# main.net
KiCad netlist of a schematic drawn in Altium Designer
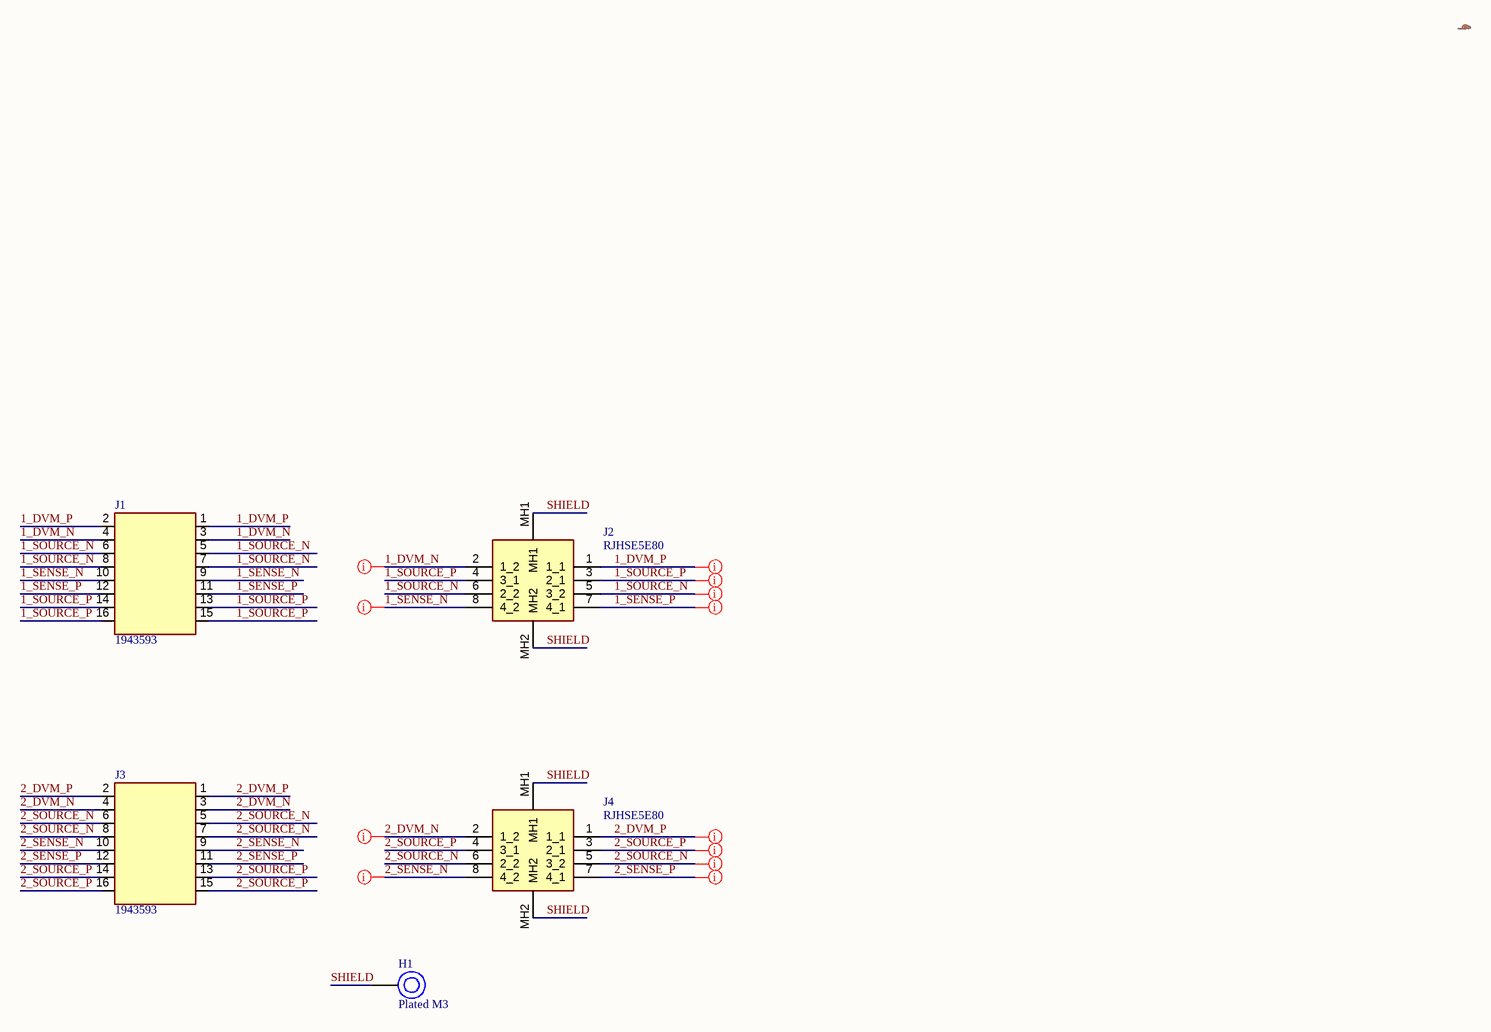
[diagram p0: main.SchDoc]

(export (version "E")
  (design (tool "Eeschema 10.0.6"))
  (components
    (comp (ref "H1")
      (value "Plated M3")
      (footprint "MountingHole_3.2mm_M3_Pad_Via_Unplated")
      (libsource (lib "jlofw") (part "mounting_hole_pad"))
    )
    (comp (ref "J1")
      (value "phoenix_1943593")
      (footprint "phoenix_1943593")
      (description "Block Header Female  5.08mm Vertical TH")
      (fields (field (name "MANUFACTURER P/N") "1943593") (field (name "MANUFACTURER") "Phoenix Contact"))
      (libsource (lib "jlofw") (part "phoenix_1943593"))
    )
    (comp (ref "J2")
      (value "amphenol_RJHSE5E80")
      (footprint "amphenol_RJHSE5E80")
      (description "RJ45 90° Angle Right Shielded")
      (fields (field (name "MANUFACTURER P/N") "RJHSE5E80") (field (name "MANUFACTURER") "Amphenol ICC"))
      (libsource (lib "jlofw") (part "amphenol_RJHSE5E80"))
    )
    (comp (ref "J3")
      (value "phoenix_1943593")
      (footprint "phoenix_1943593")
      (description "Block Header Female  5.08mm Vertical TH")
      (fields (field (name "MANUFACTURER P/N") "1943593") (field (name "MANUFACTURER") "Phoenix Contact"))
      (libsource (lib "jlofw") (part "phoenix_1943593"))
    )
    (comp (ref "J4")
      (value "amphenol_RJHSE5E80")
      (footprint "amphenol_RJHSE5E80")
      (description "RJ45 90° Angle Right Shielded")
      (fields (field (name "MANUFACTURER P/N") "RJHSE5E80") (field (name "MANUFACTURER") "Amphenol ICC"))
      (libsource (lib "jlofw") (part "amphenol_RJHSE5E80"))
    )
    (comp (ref "logo1") (value "beaver") (footprint "beaver") (libsource (lib "jlofw") (part "beaver")))
  )
  (nets
    (net (code "1") (name "/1_DVM_N") (class "Default")
      (node (ref "J1") (pin "3") (pinfunction "2.1_3") (pintype "passive"))
      (node (ref "J1") (pin "4") (pinfunction "2.2_4") (pintype "passive"))
      (node (ref "J2") (pin "2") (pinfunction "1_2_2") (pintype "passive"))
    )
    (net (code "2") (name "/1_DVM_P") (class "Default")
      (node (ref "J1") (pin "1") (pinfunction "1.1_1") (pintype "passive"))
      (node (ref "J1") (pin "2") (pinfunction "1.2_2") (pintype "passive"))
      (node (ref "J2") (pin "1") (pinfunction "1_1_1") (pintype "passive"))
    )
    (net (code "3") (name "/1_SENSE_N") (class "Default")
      (node (ref "J1") (pin "10") (pinfunction "5.2_10") (pintype "passive"))
      (node (ref "J1") (pin "9") (pinfunction "5.1_9") (pintype "passive"))
      (node (ref "J2") (pin "8") (pinfunction "4_2_8") (pintype "passive"))
    )
    (net (code "4") (name "/1_SENSE_P") (class "Default")
      (node (ref "J1") (pin "11") (pinfunction "6.1_11") (pintype "passive"))
      (node (ref "J1") (pin "12") (pinfunction "6.2_12") (pintype "passive"))
      (node (ref "J2") (pin "7") (pinfunction "4_1_7") (pintype "passive"))
    )
    (net (code "5") (name "/1_SOURCE_N") (class "Default")
      (node (ref "J1") (pin "5") (pinfunction "3.1_5") (pintype "passive"))
      (node (ref "J1") (pin "6") (pinfunction "3.2_6") (pintype "passive"))
      (node (ref "J1") (pin "7") (pinfunction "4.1_7") (pintype "passive"))
      (node (ref "J1") (pin "8") (pinfunction "4.2_8") (pintype "passive"))
      (node (ref "J2") (pin "5") (pinfunction "3_2_5") (pintype "passive"))
      (node (ref "J2") (pin "6") (pinfunction "2_2_6") (pintype "passive"))
    )
    (net (code "6") (name "/1_SOURCE_P") (class "Default")
      (node (ref "J1") (pin "13") (pinfunction "7.1_13") (pintype "passive"))
      (node (ref "J1") (pin "14") (pinfunction "7.2_14") (pintype "passive"))
      (node (ref "J1") (pin "15") (pinfunction "8.1_15") (pintype "passive"))
      (node (ref "J1") (pin "16") (pinfunction "8.2_16") (pintype "passive"))
      (node (ref "J2") (pin "3") (pinfunction "2_1_3") (pintype "passive"))
      (node (ref "J2") (pin "4") (pinfunction "3_1_4") (pintype "passive"))
    )
    (net (code "7") (name "/2_DVM_N") (class "Default")
      (node (ref "J3") (pin "3") (pinfunction "2.1_3") (pintype "passive"))
      (node (ref "J3") (pin "4") (pinfunction "2.2_4") (pintype "passive"))
      (node (ref "J4") (pin "2") (pinfunction "1_2_2") (pintype "passive"))
    )
    (net (code "8") (name "/2_DVM_P") (class "Default")
      (node (ref "J3") (pin "1") (pinfunction "1.1_1") (pintype "passive"))
      (node (ref "J3") (pin "2") (pinfunction "1.2_2") (pintype "passive"))
      (node (ref "J4") (pin "1") (pinfunction "1_1_1") (pintype "passive"))
    )
    (net (code "9") (name "/2_SENSE_N") (class "Default")
      (node (ref "J3") (pin "10") (pinfunction "5.2_10") (pintype "passive"))
      (node (ref "J3") (pin "9") (pinfunction "5.1_9") (pintype "passive"))
      (node (ref "J4") (pin "8") (pinfunction "4_2_8") (pintype "passive"))
    )
    (net (code "10") (name "/2_SENSE_P") (class "Default")
      (node (ref "J3") (pin "11") (pinfunction "6.1_11") (pintype "passive"))
      (node (ref "J3") (pin "12") (pinfunction "6.2_12") (pintype "passive"))
      (node (ref "J4") (pin "7") (pinfunction "4_1_7") (pintype "passive"))
    )
    (net (code "11") (name "/2_SOURCE_N") (class "Default")
      (node (ref "J3") (pin "5") (pinfunction "3.1_5") (pintype "passive"))
      (node (ref "J3") (pin "6") (pinfunction "3.2_6") (pintype "passive"))
      (node (ref "J3") (pin "7") (pinfunction "4.1_7") (pintype "passive"))
      (node (ref "J3") (pin "8") (pinfunction "4.2_8") (pintype "passive"))
      (node (ref "J4") (pin "5") (pinfunction "3_2_5") (pintype "passive"))
      (node (ref "J4") (pin "6") (pinfunction "2_2_6") (pintype "passive"))
    )
    (net (code "12") (name "/2_SOURCE_P") (class "Default")
      (node (ref "J3") (pin "13") (pinfunction "7.1_13") (pintype "passive"))
      (node (ref "J3") (pin "14") (pinfunction "7.2_14") (pintype "passive"))
      (node (ref "J3") (pin "15") (pinfunction "8.1_15") (pintype "passive"))
      (node (ref "J3") (pin "16") (pinfunction "8.2_16") (pintype "passive"))
      (node (ref "J4") (pin "3") (pinfunction "2_1_3") (pintype "passive"))
      (node (ref "J4") (pin "4") (pinfunction "3_1_4") (pintype "passive"))
    )
    (net (code "13") (name "/SHIELD") (class "Default")
      (node (ref "H1") (pin "1") (pinfunction "1_1") (pintype "passive"))
      (node (ref "J2") (pin "MH1") (pinfunction "MH1_MH1") (pintype "passive"))
      (node (ref "J2") (pin "MH2") (pinfunction "MH2_MH2") (pintype "passive"))
      (node (ref "J4") (pin "MH1") (pinfunction "MH1_MH1") (pintype "passive"))
      (node (ref "J4") (pin "MH2") (pinfunction "MH2_MH2") (pintype "passive"))
    )
  )
)
